# ina260.net
KiCad netlist of a schematic drawn in EAGLE
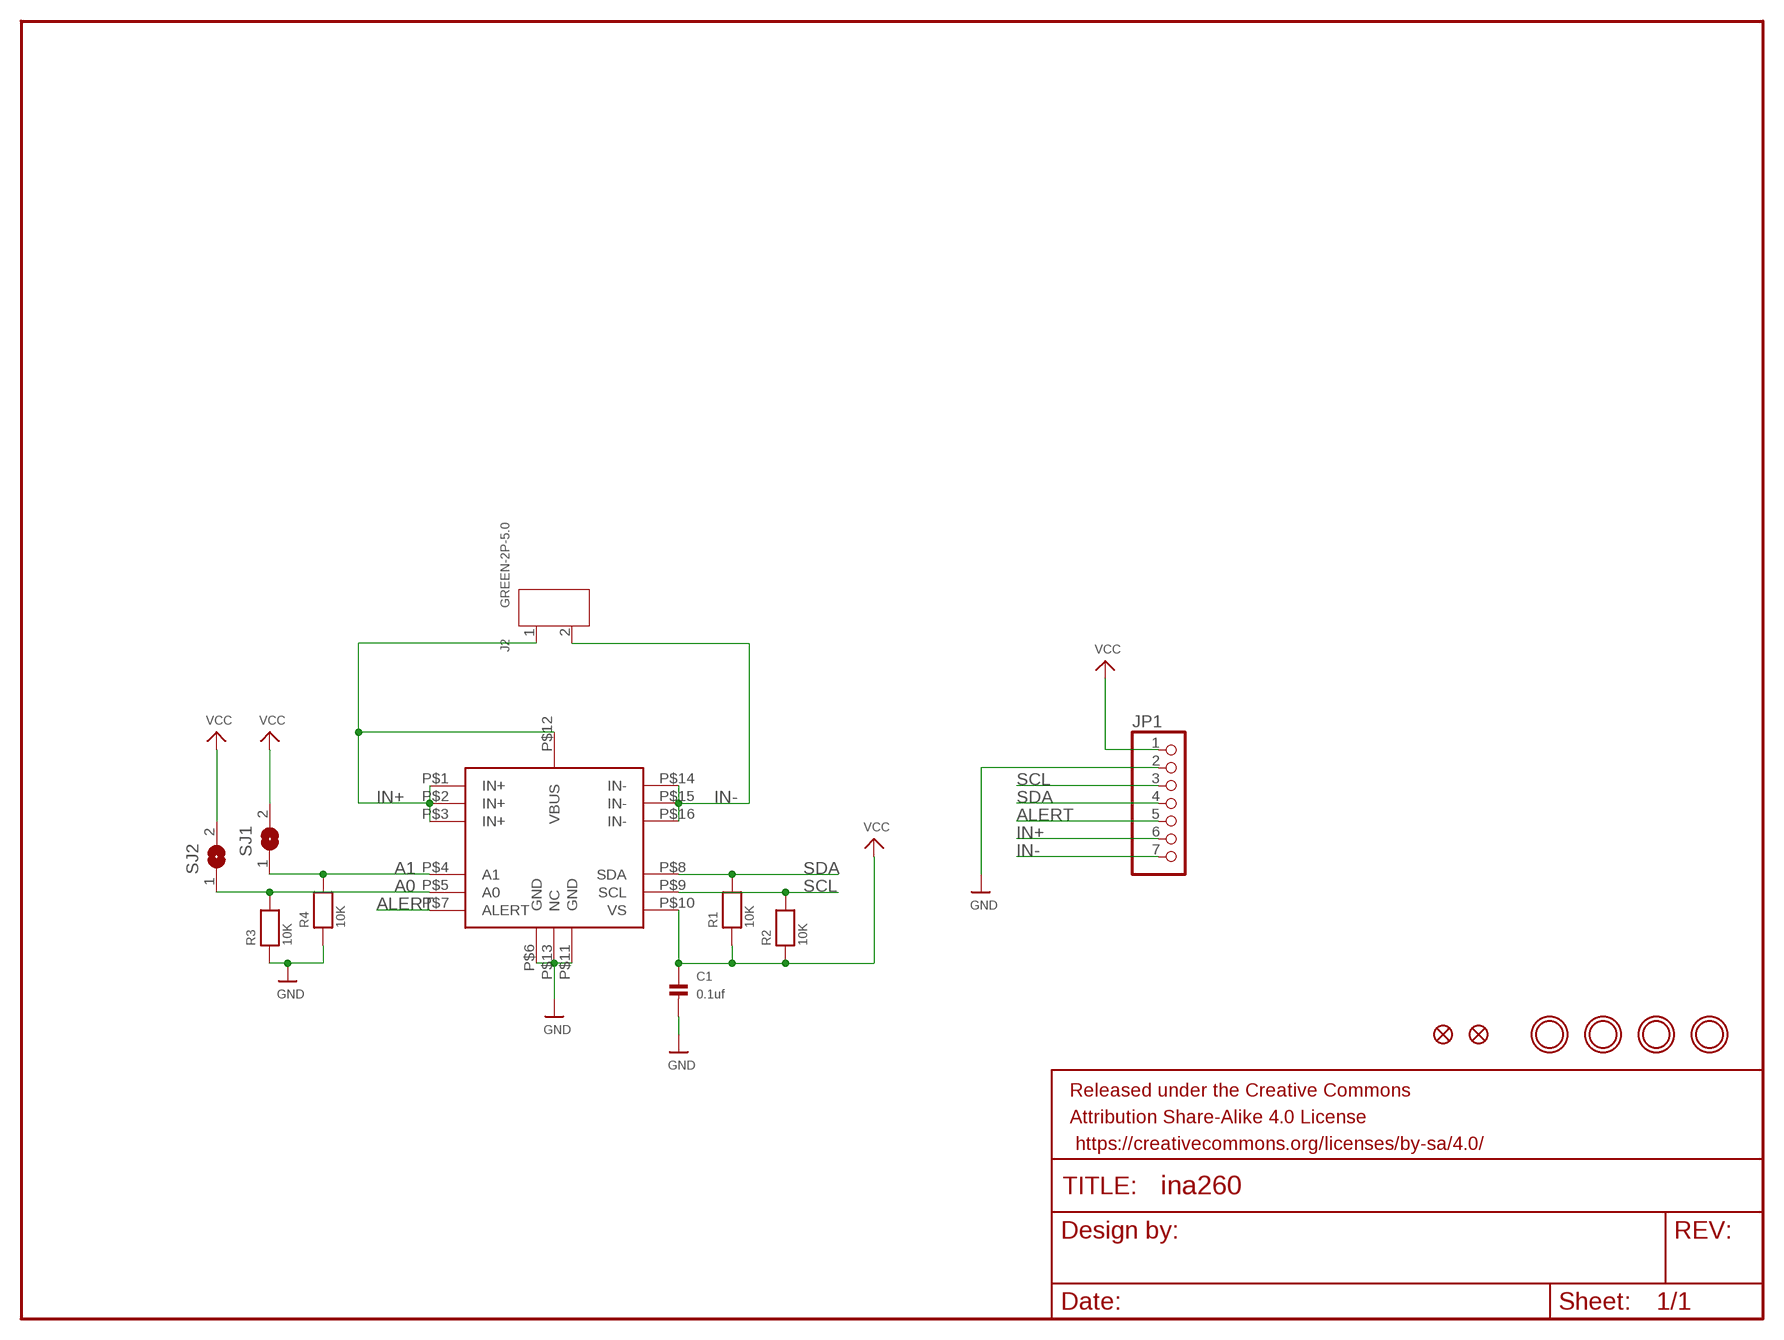
[diagram p0: schematic, sheet 1]

(export (version "E")
  (design (tool "Eeschema 10.0.6"))
  (components
    (comp (ref "C1")
      (value "0.1uf")
      (footprint "eagle-import:0805")
      (libsource (lib "eagle-import") (part "CAP_CERAMIC0805"))
    )
    (comp (ref "FID3")
      (value "MICROBUILDER_FIDUCIAL\"\"")
      (footprint "eagle-import:MICROBUILDER_FIDUCIAL_1MM")
      (libsource (lib "eagle-import") (part "MICROBUILDER_FIDUCIAL{dblquote}{dblquote}"))
    )
    (comp (ref "FID4")
      (value "MICROBUILDER_FIDUCIAL\"\"")
      (footprint "eagle-import:MICROBUILDER_FIDUCIAL_1MM")
      (libsource (lib "eagle-import") (part "MICROBUILDER_FIDUCIAL{dblquote}{dblquote}"))
    )
    (comp (ref "FRAME1")
      (value "FRAME-LETTER")
      (footprint "eagle-import:CREATIVE_COMMONS")
      (libsource (lib "eagle-import") (part "FRAME-LETTER"))
    )
    (comp (ref "J2")
      (value "GREEN-2P-5.0")
      (footprint "eagle-import:H2-5.0-10.5X8.0MM")
      (libsource (lib "eagle-import") (part "SCREW-TERMINAL-GREEN(2P-5.0)"))
    )
    (comp (ref "JP1")
      (value "HEADER-1X7ROUND")
      (footprint "eagle-import:1X07_ROUND")
      (libsource (lib "eagle-import") (part "HEADER-1X7ROUND"))
    )
    (comp (ref "R1")
      (value "10K")
      (footprint "eagle-import:0805")
      (libsource (lib "eagle-import") (part "RESISTOR0805"))
    )
    (comp (ref "R2")
      (value "10K")
      (footprint "eagle-import:0805")
      (libsource (lib "eagle-import") (part "RESISTOR0805"))
    )
    (comp (ref "R3")
      (value "10K")
      (footprint "eagle-import:0805")
      (libsource (lib "eagle-import") (part "RESISTOR0805"))
    )
    (comp (ref "R4")
      (value "10K")
      (footprint "eagle-import:0805")
      (libsource (lib "eagle-import") (part "RESISTOR0805"))
    )
    (comp (ref "SJ1")
      (value "SOLDERJUMPERREFLOW_NOPASTE")
      (footprint "eagle-import:SOLDERJUMPER_REFLOW_NOPASTE")
      (libsource (lib "eagle-import") (part "SOLDERJUMPERREFLOW_NOPASTE"))
    )
    (comp (ref "SJ2")
      (value "SOLDERJUMPERREFLOW_NOPASTE")
      (footprint "eagle-import:SOLDERJUMPER_REFLOW_NOPASTE")
      (libsource (lib "eagle-import") (part "SOLDERJUMPERREFLOW_NOPASTE"))
    )
    (comp (ref "U$1")
      (value "INA260")
      (footprint "eagle-import:INA260_TSSOP16")
      (libsource (lib "eagle-import") (part "INA260"))
    )
    (comp (ref "U$5")
      (value "MOUNTINGHOLE2.5")
      (footprint "eagle-import:MOUNTINGHOLE_2.5_PLATED")
      (libsource (lib "eagle-import") (part "MOUNTINGHOLE2.5"))
    )
    (comp (ref "U$6")
      (value "MOUNTINGHOLE2.5")
      (footprint "eagle-import:MOUNTINGHOLE_2.5_PLATED")
      (libsource (lib "eagle-import") (part "MOUNTINGHOLE2.5"))
    )
    (comp (ref "U$7")
      (value "MOUNTINGHOLE2.5")
      (footprint "eagle-import:MOUNTINGHOLE_2.5_PLATED")
      (libsource (lib "eagle-import") (part "MOUNTINGHOLE2.5"))
    )
    (comp (ref "U$8")
      (value "MOUNTINGHOLE2.5")
      (footprint "eagle-import:MOUNTINGHOLE_2.5_PLATED")
      (libsource (lib "eagle-import") (part "MOUNTINGHOLE2.5"))
    )
  )
  (nets
    (net (code "1") (name "/A0") (class "Default")
      (node (ref "R3") (pin "2") (pinfunction "2_2") (pintype "passive"))
      (node (ref "SJ2") (pin "1") (pinfunction "1_1") (pintype "passive"))
      (node (ref "U$1") (pin "P$5") (pinfunction "A0_P$5") (pintype "bidirectional"))
    )
    (net (code "2") (name "/A1") (class "Default")
      (node (ref "R4") (pin "2") (pinfunction "2_2") (pintype "passive"))
      (node (ref "SJ1") (pin "1") (pinfunction "1_1") (pintype "passive"))
      (node (ref "U$1") (pin "P$4") (pinfunction "A1_P$4") (pintype "bidirectional"))
    )
    (net (code "3") (name "/ALERT") (class "Default")
      (node (ref "JP1") (pin "5") (pinfunction "5_5") (pintype "passive"))
      (node (ref "U$1") (pin "P$7") (pinfunction "ALERT_P$7") (pintype "bidirectional"))
    )
    (net (code "4") (name "/IN+") (class "Default")
      (node (ref "J2") (pin "1") (pinfunction "1_1") (pintype "bidirectional"))
      (node (ref "JP1") (pin "6") (pinfunction "6_6") (pintype "passive"))
      (node (ref "U$1") (pin "P$1") (pinfunction "IN+_P$1") (pintype "bidirectional"))
      (node (ref "U$1") (pin "P$12") (pinfunction "VBUS_P$12") (pintype "bidirectional"))
      (node (ref "U$1") (pin "P$2") (pinfunction "IN+_P$2") (pintype "bidirectional"))
      (node (ref "U$1") (pin "P$3") (pinfunction "IN+_P$3") (pintype "bidirectional"))
    )
    (net (code "5") (name "/IN-") (class "Default")
      (node (ref "J2") (pin "2") (pinfunction "2_2") (pintype "bidirectional"))
      (node (ref "JP1") (pin "7") (pinfunction "7_7") (pintype "passive"))
      (node (ref "U$1") (pin "P$14") (pinfunction "IN-_P$14") (pintype "bidirectional"))
      (node (ref "U$1") (pin "P$15") (pinfunction "IN-_P$15") (pintype "bidirectional"))
      (node (ref "U$1") (pin "P$16") (pinfunction "IN-_P$16") (pintype "bidirectional"))
    )
    (net (code "6") (name "/SCL") (class "Default")
      (node (ref "JP1") (pin "3") (pinfunction "3_3") (pintype "passive"))
      (node (ref "R2") (pin "2") (pinfunction "2_2") (pintype "passive"))
      (node (ref "U$1") (pin "P$9") (pinfunction "SCL_P$9") (pintype "bidirectional"))
    )
    (net (code "7") (name "/SDA") (class "Default")
      (node (ref "JP1") (pin "4") (pinfunction "4_4") (pintype "passive"))
      (node (ref "R1") (pin "2") (pinfunction "2_2") (pintype "passive"))
      (node (ref "U$1") (pin "P$8") (pinfunction "SDA_P$8") (pintype "bidirectional"))
    )
    (net (code "8") (name "GND") (class "Default")
      (node (ref "C1") (pin "2") (pinfunction "P$2_2") (pintype "passive"))
      (node (ref "JP1") (pin "2") (pinfunction "2_2") (pintype "passive"))
      (node (ref "R3") (pin "1") (pinfunction "1_1") (pintype "passive"))
      (node (ref "R4") (pin "1") (pinfunction "1_1") (pintype "passive"))
      (node (ref "U$1") (pin "P$11") (pinfunction "GND_P$11") (pintype "bidirectional"))
      (node (ref "U$1") (pin "P$13") (pinfunction "NC_P$13") (pintype "bidirectional"))
      (node (ref "U$1") (pin "P$6") (pinfunction "GND_P$6") (pintype "bidirectional"))
    )
    (net (code "9") (name "VCC") (class "Default")
      (node (ref "C1") (pin "1") (pinfunction "P$1_1") (pintype "passive"))
      (node (ref "JP1") (pin "1") (pinfunction "1_1") (pintype "passive"))
      (node (ref "R1") (pin "1") (pinfunction "1_1") (pintype "passive"))
      (node (ref "R2") (pin "1") (pinfunction "1_1") (pintype "passive"))
      (node (ref "SJ1") (pin "2") (pinfunction "2_2") (pintype "passive"))
      (node (ref "SJ2") (pin "2") (pinfunction "2_2") (pintype "passive"))
      (node (ref "U$1") (pin "P$10") (pinfunction "VS_P$10") (pintype "bidirectional"))
    )
  )
)
